# eos-mc-one.net
KiCad netlist of a schematic drawn in EAGLE
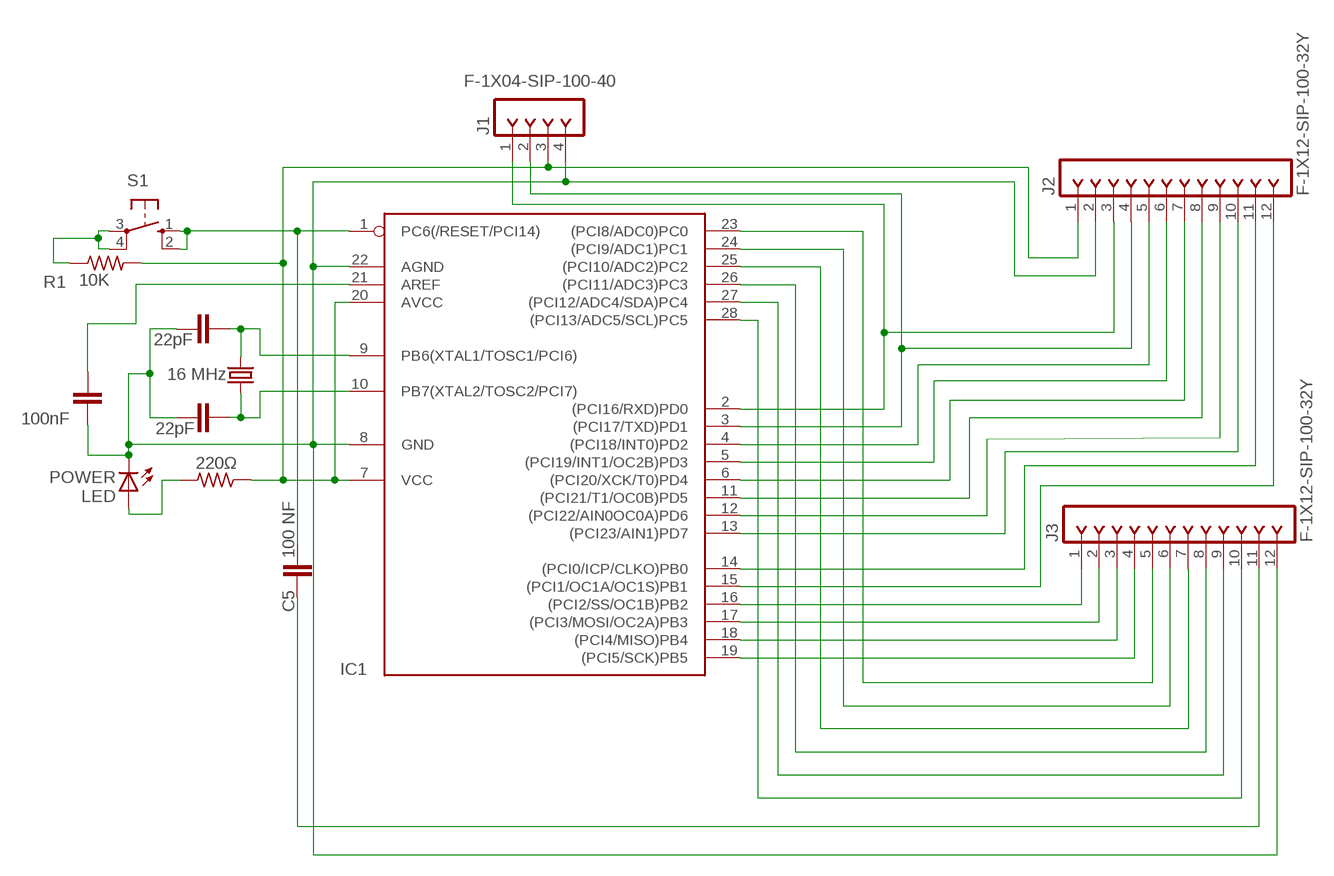
[diagram p0: schematic, sheet 1]

(export (version "E")
  (design (tool "Eeschema 10.0.6"))
  (components
    (comp (ref "C1")
      (value "22pF")
      (footprint "eagle-import:C2.5-3")
      (libsource (lib "eagle-import") (part "C2,5-3"))
    )
    (comp (ref "C2")
      (value "22pF")
      (footprint "eagle-import:C2.5-3")
      (libsource (lib "eagle-import") (part "C2,5-3"))
    )
    (comp (ref "C3")
      (value "100nF")
      (footprint "eagle-import:C2.5-3")
      (libsource (lib "eagle-import") (part "C2,5-3"))
    )
    (comp (ref "C5")
      (value "100 NF")
      (footprint "eagle-import:C2.5-3")
      (libsource (lib "eagle-import") (part "C2,5-3"))
    )
    (comp (ref "IC1")
      (value "ATMEGA328-20P")
      (footprint "eagle-import:DIL28-3")
      (libsource (lib "eagle-import") (part "ATMEGA328P-20"))
    )
    (comp (ref "J1")
      (value "F-1X04-SIP-100-40")
      (footprint "eagle-import:SIP-100-04-40")
      (libsource (lib "eagle-import") (part "F-1X04-SIP-100-40"))
    )
    (comp (ref "J2")
      (value "F-1X12-SIP-100-32Y")
      (footprint "eagle-import:SIP-100-12-32Y")
      (libsource (lib "eagle-import") (part "F-1X12-SIP-100-32Y"))
    )
    (comp (ref "J3")
      (value "F-1X12-SIP-100-32Y")
      (footprint "eagle-import:SIP-100-12-32Y")
      (libsource (lib "eagle-import") (part "F-1X12-SIP-100-32Y"))
    )
    (comp (ref "LED3")
      (value "LED5MM")
      (footprint "eagle-import:LED5MM")
      (libsource (lib "eagle-import") (part "LED5MM"))
    )
    (comp (ref "Q1")
      (value "16 MHz")
      (footprint "eagle-import:HC49_S")
      (libsource (lib "eagle-import") (part "CRYSTALHC49S"))
    )
    (comp (ref "R1")
      (value "10K")
      (footprint "eagle-import:0805-THM")
      (libsource (lib "eagle-import") (part "FLIPFLOP-RES"))
    )
    (comp (ref "R5")
      (value "220Ω")
      (footprint "eagle-import:0805-THM")
      (libsource (lib "eagle-import") (part "FLIPFLOP-RES"))
    )
    (comp (ref "S1")
      (value "10-XX")
      (footprint "eagle-import:B3F-10XX")
      (fields (field (name "MPN") "B3F-1000"))
      (libsource (lib "eagle-import") (part "10-XX"))
    )
  )
  (nets
    (net (code "1") (name "Net-(C5-Pad1)") (class "Default")
      (node (ref "C5") (pin "1") (pinfunction "1_1") (pintype "passive"))
      (node (ref "J3") (pin "11") (pinfunction "11_11") (pintype "passive"))
    )
    (net (code "2") (name "Net-(IC1-(PCI0{slash}ICP{slash}CLKO)PB0)") (class "Default")
      (node (ref "IC1") (pin "14") (pinfunction "(PCI0/ICP/CLKO)PB0_14") (pintype "bidirectional"))
      (node (ref "J2") (pin "11") (pinfunction "11_11") (pintype "passive"))
    )
    (net (code "3") (name "Net-(IC1-(PCI1{slash}OC1A{slash}OC1S)PB1)") (class "Default")
      (node (ref "IC1") (pin "15") (pinfunction "(PCI1/OC1A/OC1S)PB1_15") (pintype "bidirectional"))
      (node (ref "J2") (pin "12") (pinfunction "12_12") (pintype "passive"))
    )
    (net (code "4") (name "Net-(IC1-(PCI2{slash}SS{slash}OC1B)PB2)") (class "Default")
      (node (ref "IC1") (pin "16") (pinfunction "(PCI2/SS/OC1B)PB2_16") (pintype "bidirectional"))
      (node (ref "J3") (pin "1") (pinfunction "1_1") (pintype "passive"))
    )
    (net (code "5") (name "Net-(IC1-(PCI3{slash}MOSI{slash}OC2A)PB3)") (class "Default")
      (node (ref "IC1") (pin "17") (pinfunction "(PCI3/MOSI/OC2A)PB3_17") (pintype "bidirectional"))
      (node (ref "J3") (pin "2") (pinfunction "2_2") (pintype "passive"))
    )
    (net (code "6") (name "Net-(IC1-(PCI4{slash}MISO)PB4)") (class "Default")
      (node (ref "IC1") (pin "18") (pinfunction "(PCI4/MISO)PB4_18") (pintype "bidirectional"))
      (node (ref "J3") (pin "3") (pinfunction "3_3") (pintype "passive"))
    )
    (net (code "7") (name "Net-(IC1-(PCI5{slash}SCK)PB5)") (class "Default")
      (node (ref "IC1") (pin "19") (pinfunction "(PCI5/SCK)PB5_19") (pintype "bidirectional"))
      (node (ref "J3") (pin "4") (pinfunction "4_4") (pintype "passive"))
    )
    (net (code "8") (name "Net-(IC1-(PCI8{slash}ADC0)PC0)") (class "Default")
      (node (ref "IC1") (pin "23") (pinfunction "(PCI8/ADC0)PC0_23") (pintype "bidirectional"))
      (node (ref "J3") (pin "5") (pinfunction "5_5") (pintype "passive"))
    )
    (net (code "9") (name "Net-(IC1-(PCI9{slash}ADC1)PC1)") (class "Default")
      (node (ref "IC1") (pin "24") (pinfunction "(PCI9/ADC1)PC1_24") (pintype "bidirectional"))
      (node (ref "J3") (pin "6") (pinfunction "6_6") (pintype "passive"))
    )
    (net (code "10") (name "Net-(IC1-(PCI10{slash}ADC2)PC2)") (class "Default")
      (node (ref "IC1") (pin "25") (pinfunction "(PCI10/ADC2)PC2_25") (pintype "bidirectional"))
      (node (ref "J3") (pin "7") (pinfunction "7_7") (pintype "passive"))
    )
    (net (code "11") (name "Net-(IC1-(PCI11{slash}ADC3)PC3)") (class "Default")
      (node (ref "IC1") (pin "26") (pinfunction "(PCI11/ADC3)PC3_26") (pintype "bidirectional"))
      (node (ref "J3") (pin "8") (pinfunction "8_8") (pintype "passive"))
    )
    (net (code "12") (name "Net-(IC1-(PCI12{slash}ADC4{slash}SDA)PC4)") (class "Default")
      (node (ref "IC1") (pin "27") (pinfunction "(PCI12/ADC4/SDA)PC4_27") (pintype "bidirectional"))
      (node (ref "J3") (pin "9") (pinfunction "9_9") (pintype "passive"))
    )
    (net (code "13") (name "Net-(IC1-(PCI13{slash}ADC5{slash}SCL)PC5)") (class "Default")
      (node (ref "IC1") (pin "28") (pinfunction "(PCI13/ADC5/SCL)PC5_28") (pintype "bidirectional"))
      (node (ref "J3") (pin "10") (pinfunction "10_10") (pintype "passive"))
    )
    (net (code "14") (name "Net-(IC1-(PCI16{slash}RXD)PD0)") (class "Default")
      (node (ref "IC1") (pin "2") (pinfunction "(PCI16/RXD)PD0_2") (pintype "bidirectional"))
      (node (ref "J1") (pin "1") (pinfunction "1_1") (pintype "passive"))
      (node (ref "J2") (pin "3") (pinfunction "3_3") (pintype "passive"))
    )
    (net (code "15") (name "Net-(IC1-(PCI17{slash}TXD)PD1)") (class "Default")
      (node (ref "IC1") (pin "3") (pinfunction "(PCI17/TXD)PD1_3") (pintype "bidirectional"))
      (node (ref "J1") (pin "2") (pinfunction "2_2") (pintype "passive"))
      (node (ref "J2") (pin "4") (pinfunction "4_4") (pintype "passive"))
    )
    (net (code "16") (name "Net-(IC1-(PCI18{slash}INT0)PD2)") (class "Default")
      (node (ref "IC1") (pin "4") (pinfunction "(PCI18/INT0)PD2_4") (pintype "bidirectional"))
      (node (ref "J2") (pin "5") (pinfunction "5_5") (pintype "passive"))
    )
    (net (code "17") (name "Net-(IC1-(PCI19{slash}INT1{slash}OC2B)PD3)") (class "Default")
      (node (ref "IC1") (pin "5") (pinfunction "(PCI19/INT1/OC2B)PD3_5") (pintype "bidirectional"))
      (node (ref "J2") (pin "6") (pinfunction "6_6") (pintype "passive"))
    )
    (net (code "18") (name "Net-(IC1-(PCI20{slash}XCK{slash}T0)PD4)") (class "Default")
      (node (ref "IC1") (pin "6") (pinfunction "(PCI20/XCK/T0)PD4_6") (pintype "bidirectional"))
      (node (ref "J2") (pin "7") (pinfunction "7_7") (pintype "passive"))
    )
    (net (code "19") (name "Net-(IC1-(PCI21{slash}T1{slash}OC0B)PD5)") (class "Default")
      (node (ref "IC1") (pin "11") (pinfunction "(PCI21/T1/OC0B)PD5_11") (pintype "bidirectional"))
      (node (ref "J2") (pin "8") (pinfunction "8_8") (pintype "passive"))
    )
    (net (code "20") (name "Net-(IC1-(PCI22{slash}AIN0OC0A)PD6)") (class "Default")
      (node (ref "IC1") (pin "12") (pinfunction "(PCI22/AIN0OC0A)PD6_12") (pintype "bidirectional"))
      (node (ref "J2") (pin "9") (pinfunction "9_9") (pintype "passive"))
    )
    (net (code "21") (name "Net-(IC1-(PCI23{slash}AIN1)PD7)") (class "Default")
      (node (ref "IC1") (pin "13") (pinfunction "(PCI23/AIN1)PD7_13") (pintype "bidirectional"))
      (node (ref "J2") (pin "10") (pinfunction "10_10") (pintype "passive"))
    )
    (net (code "22") (name "Net-(IC1-AGND)") (class "Default")
      (node (ref "C1") (pin "1") (pinfunction "1_1") (pintype "passive"))
      (node (ref "C2") (pin "1") (pinfunction "1_1") (pintype "passive"))
      (node (ref "C3") (pin "1") (pinfunction "1_1") (pintype "passive"))
      (node (ref "IC1") (pin "22") (pinfunction "AGND_22") (pintype "bidirectional"))
      (node (ref "IC1") (pin "8") (pinfunction "GND_8") (pintype "bidirectional"))
      (node (ref "J1") (pin "4") (pinfunction "4_4") (pintype "passive"))
      (node (ref "J2") (pin "2") (pinfunction "2_2") (pintype "passive"))
      (node (ref "J3") (pin "12") (pinfunction "12_12") (pintype "passive"))
      (node (ref "LED3") (pin "K") (pinfunction "C_K") (pintype "passive"))
    )
    (net (code "23") (name "Net-(IC1-AREF)") (class "Default")
      (node (ref "C3") (pin "2") (pinfunction "2_2") (pintype "passive"))
      (node (ref "IC1") (pin "21") (pinfunction "AREF_21") (pintype "bidirectional"))
    )
    (net (code "24") (name "Net-(IC1-AVCC)") (class "Default")
      (node (ref "IC1") (pin "20") (pinfunction "AVCC_20") (pintype "bidirectional"))
      (node (ref "IC1") (pin "7") (pinfunction "VCC_7") (pintype "bidirectional"))
      (node (ref "J1") (pin "3") (pinfunction "3_3") (pintype "passive"))
      (node (ref "J2") (pin "1") (pinfunction "1_1") (pintype "passive"))
      (node (ref "R1") (pin "2") (pinfunction "2_2") (pintype "passive"))
      (node (ref "R5") (pin "1") (pinfunction "1_1") (pintype "passive"))
    )
    (net (code "25") (name "Net-(IC1-PB6(XTAL1{slash}TOSC1{slash}PCI6))") (class "Default")
      (node (ref "C1") (pin "2") (pinfunction "2_2") (pintype "passive"))
      (node (ref "IC1") (pin "9") (pinfunction "PB6(XTAL1/TOSC1/PCI6)_9") (pintype "bidirectional"))
      (node (ref "Q1") (pin "2") (pinfunction "2_2") (pintype "passive"))
    )
    (net (code "26") (name "Net-(IC1-PB7(XTAL2{slash}TOSC2{slash}PCI7))") (class "Default")
      (node (ref "C2") (pin "2") (pinfunction "2_2") (pintype "passive"))
      (node (ref "IC1") (pin "10") (pinfunction "PB7(XTAL2/TOSC2/PCI7)_10") (pintype "bidirectional"))
      (node (ref "Q1") (pin "1") (pinfunction "1_1") (pintype "passive"))
    )
    (net (code "27") (name "Net-(IC1-PC6({slash}RESET{slash}PCI14))") (class "Default")
      (node (ref "C5") (pin "2") (pinfunction "2_2") (pintype "passive"))
      (node (ref "IC1") (pin "1") (pinfunction "PC6(/RESET/PCI14)_1") (pintype "bidirectional"))
      (node (ref "S1") (pin "1") (pinfunction "S_1") (pintype "passive"))
      (node (ref "S1") (pin "2") (pinfunction "S1_2") (pintype "passive"))
    )
    (net (code "28") (name "Net-(LED3-PadA)") (class "Default")
      (node (ref "LED3") (pin "A") (pinfunction "A_A") (pintype "passive"))
      (node (ref "R5") (pin "2") (pinfunction "2_2") (pintype "passive"))
    )
    (net (code "29") (name "Net-(S1-P)") (class "Default")
      (node (ref "R1") (pin "1") (pinfunction "1_1") (pintype "passive"))
      (node (ref "S1") (pin "3") (pinfunction "P_3") (pintype "passive"))
      (node (ref "S1") (pin "4") (pinfunction "P1_4") (pintype "passive"))
    )
  )
)
